# USB.net
KiCad netlist of a schematic drawn in Altium Designer
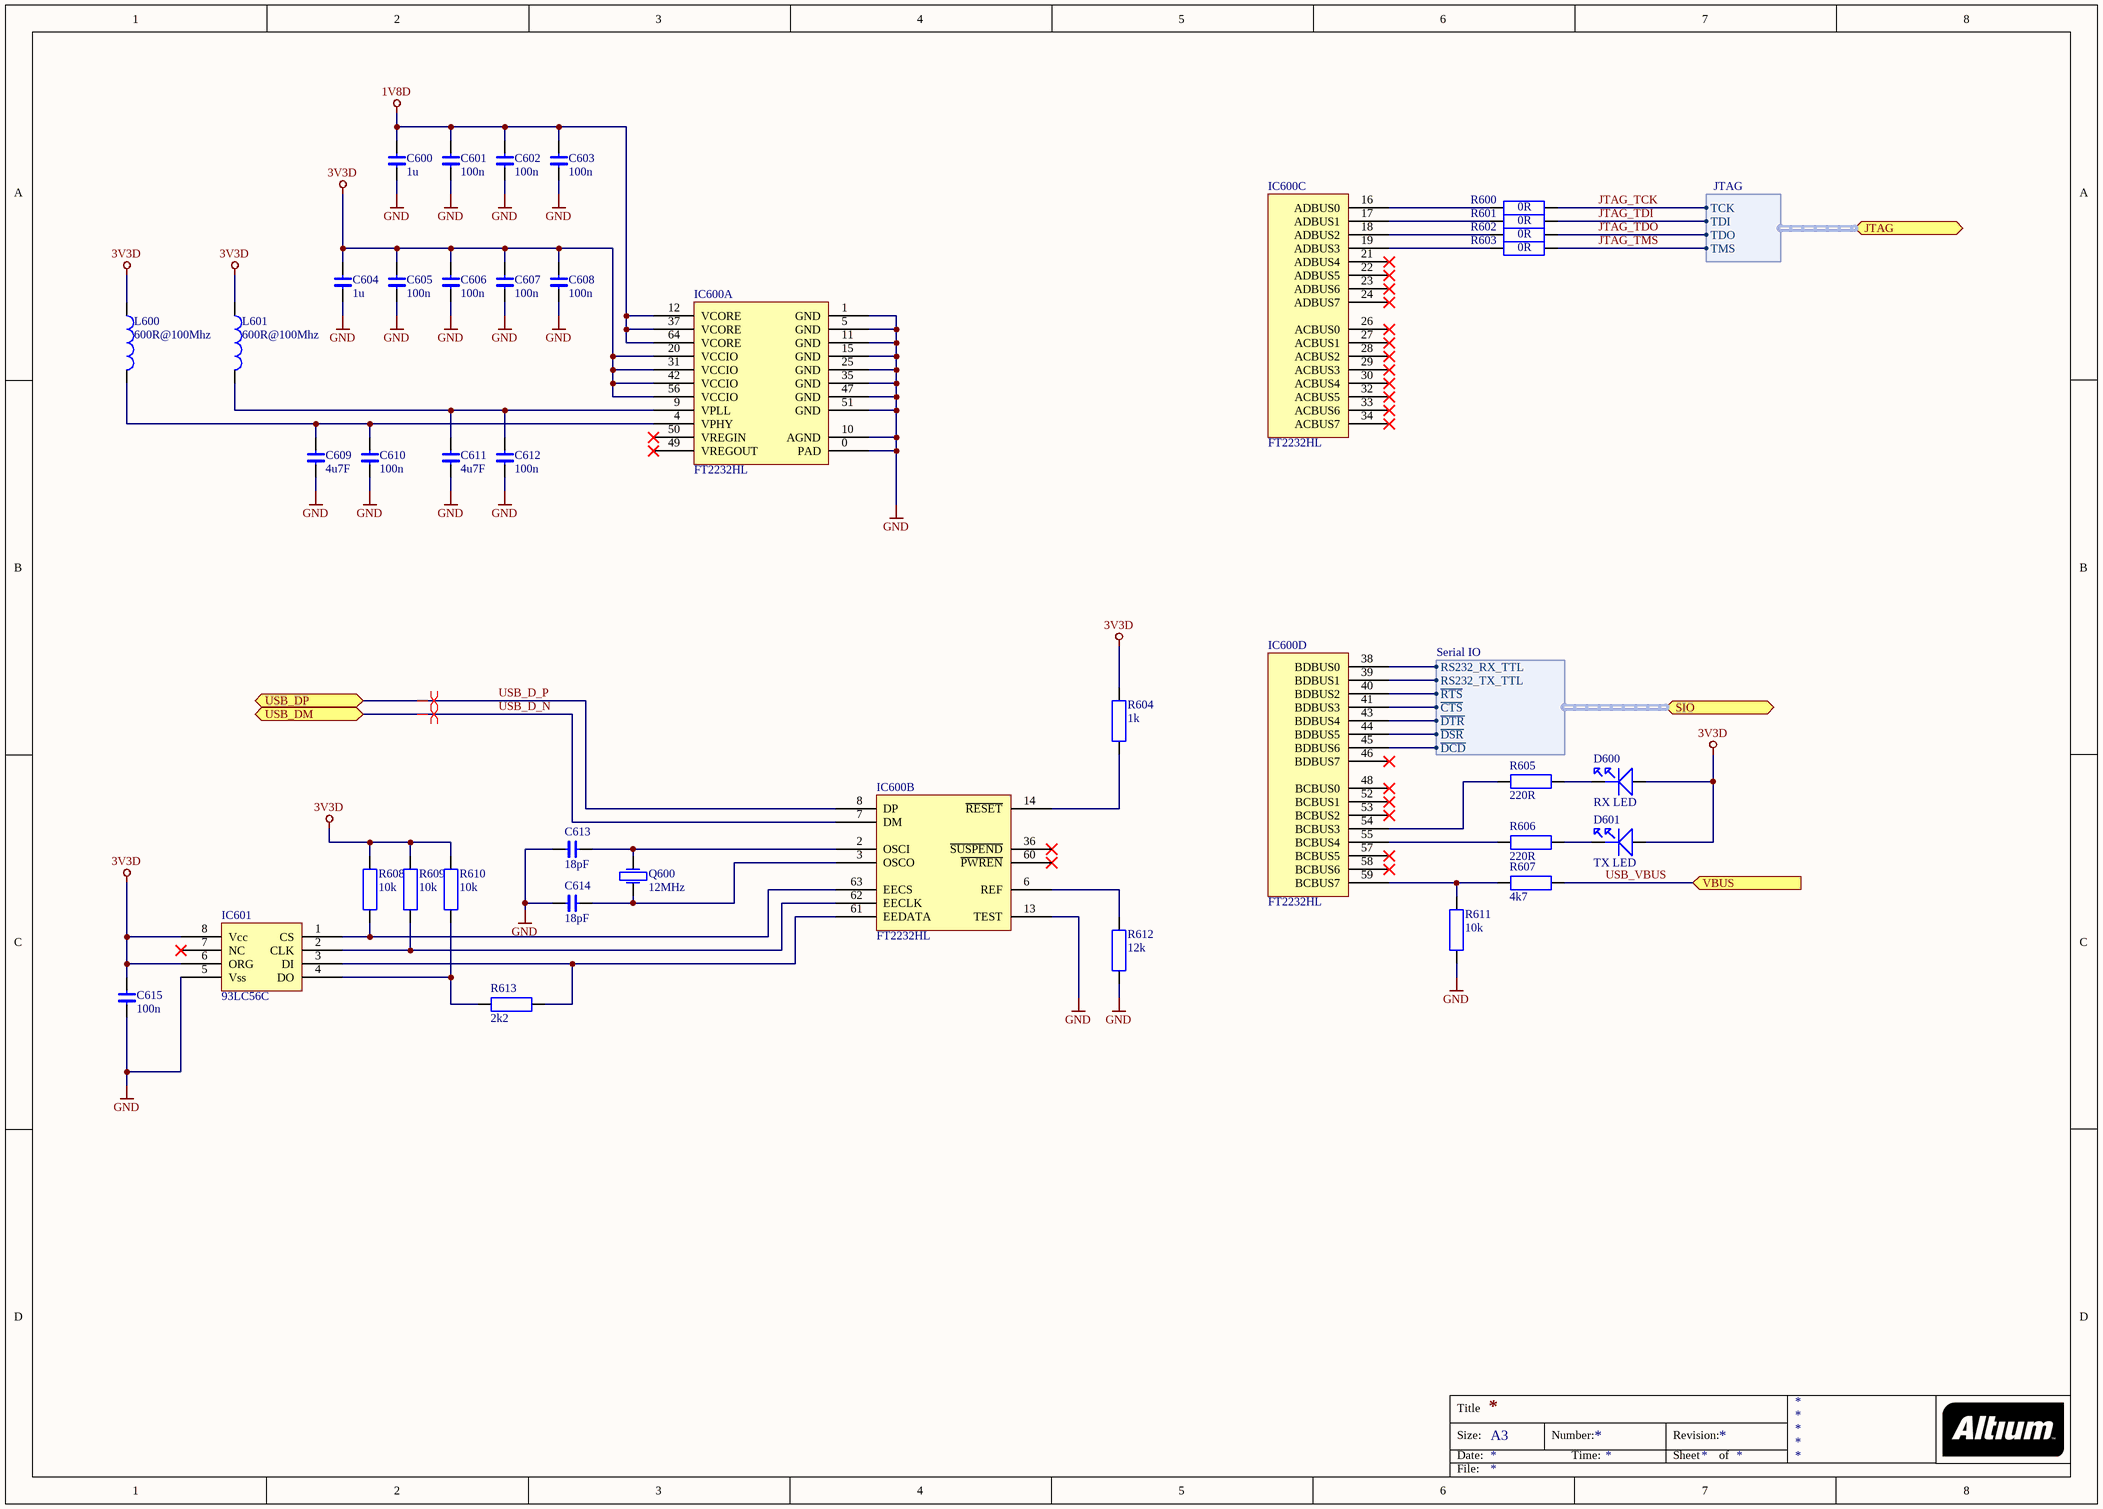
[diagram p0: USB.SchDoc]

(export (version "E")
  (design (tool "Eeschema 10.0.6"))
  (components
    (comp (ref "C600")
      (value "1u")
      (footprint "0603 SMALL OUTLINE")
      (description "C")
      (libsource (lib "RCL") (part "C"))
    )
    (comp (ref "C601")
      (value "100n")
      (footprint "0603 SMALL OUTLINE")
      (description "C")
      (libsource (lib "RCL") (part "C"))
    )
    (comp (ref "C602")
      (value "100n")
      (footprint "0603 SMALL OUTLINE")
      (description "C")
      (libsource (lib "RCL") (part "C"))
    )
    (comp (ref "C603")
      (value "100n")
      (footprint "0603 SMALL OUTLINE")
      (description "C")
      (libsource (lib "RCL") (part "C"))
    )
    (comp (ref "C604")
      (value "1u")
      (footprint "0603 SMALL OUTLINE")
      (description "C")
      (libsource (lib "RCL") (part "C"))
    )
    (comp (ref "C605")
      (value "100n")
      (footprint "0603 SMALL OUTLINE")
      (description "C")
      (libsource (lib "RCL") (part "C"))
    )
    (comp (ref "C606")
      (value "100n")
      (footprint "0603 SMALL OUTLINE")
      (description "C")
      (libsource (lib "RCL") (part "C"))
    )
    (comp (ref "C607")
      (value "100n")
      (footprint "0603 SMALL OUTLINE")
      (description "C")
      (libsource (lib "RCL") (part "C"))
    )
    (comp (ref "C608")
      (value "100n")
      (footprint "0603 SMALL OUTLINE")
      (description "C")
      (libsource (lib "RCL") (part "C"))
    )
    (comp (ref "C609")
      (value "4u7F")
      (footprint "0603 SMALL OUTLINE")
      (description "C")
      (libsource (lib "RCL") (part "C"))
    )
    (comp (ref "C610")
      (value "100n")
      (footprint "0603 SMALL OUTLINE")
      (description "C")
      (libsource (lib "RCL") (part "C"))
    )
    (comp (ref "C611")
      (value "4u7F")
      (footprint "0603 SMALL OUTLINE")
      (description "C")
      (libsource (lib "RCL") (part "C"))
    )
    (comp (ref "C612")
      (value "100n")
      (footprint "0603 SMALL OUTLINE")
      (description "C")
      (libsource (lib "RCL") (part "C"))
    )
    (comp (ref "C613")
      (value "18pF")
      (footprint "0603 SMALL OUTLINE")
      (description "C")
      (libsource (lib "RCL") (part "C"))
    )
    (comp (ref "C614")
      (value "18pF")
      (footprint "0603 SMALL OUTLINE")
      (description "C")
      (libsource (lib "RCL") (part "C"))
    )
    (comp (ref "C615")
      (value "100n")
      (footprint "0603 SMALL OUTLINE")
      (description "C")
      (libsource (lib "RCL") (part "C"))
    )
    (comp (ref "D600")
      (value "RX LED")
      (footprint "LED SMD 0603")
      (description "WURTH 150060VS75000")
      (libsource (lib "OPTO1") (part "LED SMD"))
    )
    (comp (ref "D601")
      (value "TX LED")
      (footprint "LED SMD 0603")
      (description "WURTH 150060VS75000")
      (libsource (lib "OPTO1") (part "LED SMD"))
    )
    (comp (ref "IC600")
      (value "FT2232HL")
      (footprint "64QFN")
      (description "DUAL HIGH SPEED USB TO MULTIPURPOSE UART/FIFO IC")
      (libsource (lib "Private") (part "FT2232HL"))
    )
    (comp (ref "IC601")
      (value "93LC56C")
      (footprint "MSOP8")
      (description "2K Microwire Compatible Serial EEPROM")
      (libsource (lib "Private") (part "93LC56C"))
    )
    (comp (ref "L600") (value "600R@100Mhz") (footprint "0805") (libsource (lib "RCL") (part "L")))
    (comp (ref "L601") (value "600R@100Mhz") (footprint "0805") (libsource (lib "RCL") (part "L")))
    (comp (ref "Q600")
      (value "12MHz")
      (footprint "SMD_XTAL_5x3.2")
      (description "XX MHz")
      (libsource (lib "RCL") (part "CRYSTAL"))
    )
    (comp (ref "R600")
      (value "0R")
      (footprint "0603 SMALL OUTLINE")
      (description "R")
      (libsource (lib "RCL") (part "R"))
    )
    (comp (ref "R601")
      (value "0R")
      (footprint "0603 SMALL OUTLINE")
      (description "R")
      (libsource (lib "RCL") (part "R"))
    )
    (comp (ref "R602")
      (value "0R")
      (footprint "0603 SMALL OUTLINE")
      (description "R")
      (libsource (lib "RCL") (part "R"))
    )
    (comp (ref "R603")
      (value "0R")
      (footprint "0603 SMALL OUTLINE")
      (description "R")
      (libsource (lib "RCL") (part "R"))
    )
    (comp (ref "R604")
      (value "1k")
      (footprint "0603 SMALL OUTLINE")
      (description "R")
      (libsource (lib "RCL") (part "R"))
    )
    (comp (ref "R605")
      (value "220R")
      (footprint "0603 SMALL OUTLINE")
      (description "R")
      (libsource (lib "RCL") (part "R"))
    )
    (comp (ref "R606")
      (value "220R")
      (footprint "0603 SMALL OUTLINE")
      (description "R")
      (libsource (lib "RCL") (part "R"))
    )
    (comp (ref "R607")
      (value "4k7")
      (footprint "0603 SMALL OUTLINE")
      (description "R")
      (libsource (lib "RCL") (part "R"))
    )
    (comp (ref "R608")
      (value "10k")
      (footprint "0603 SMALL OUTLINE")
      (description "R")
      (libsource (lib "RCL") (part "R"))
    )
    (comp (ref "R609")
      (value "10k")
      (footprint "0603 SMALL OUTLINE")
      (description "R")
      (libsource (lib "RCL") (part "R"))
    )
    (comp (ref "R610")
      (value "10k")
      (footprint "0603 SMALL OUTLINE")
      (description "R")
      (libsource (lib "RCL") (part "R"))
    )
    (comp (ref "R611")
      (value "10k")
      (footprint "0603 SMALL OUTLINE")
      (description "R")
      (libsource (lib "RCL") (part "R"))
    )
    (comp (ref "R612")
      (value "12k")
      (footprint "0603 SMALL OUTLINE")
      (description "R")
      (libsource (lib "RCL") (part "R"))
    )
    (comp (ref "R613")
      (value "2k2")
      (footprint "0603 SMALL OUTLINE")
      (description "R")
      (libsource (lib "RCL") (part "R"))
    )
  )
  (nets
    (net (code "4") (name "/JTAG_TCK") (class "Default")
      (node (ref "R600") (pin "2") (pinfunction "2_2") (pintype "passive"))
    )
    (net (code "5") (name "/JTAG_TDI") (class "Default")
      (node (ref "R601") (pin "2") (pinfunction "2_2") (pintype "passive"))
    )
    (net (code "6") (name "/JTAG_TDO") (class "Default")
      (node (ref "R602") (pin "2") (pinfunction "2_2") (pintype "passive"))
    )
    (net (code "7") (name "/JTAG_TMS") (class "Default")
      (node (ref "R603") (pin "2") (pinfunction "2_2") (pintype "passive"))
    )
    (net (code "8") (name "/RS232_RX_TTL") (class "Default")
      (node (ref "IC600") (pin "38") (pinfunction "BDBUS0_38") (pintype "passive"))
    )
    (net (code "9") (name "/RS232_TX_TTL") (class "Default")
      (node (ref "IC600") (pin "39") (pinfunction "BDBUS1_39") (pintype "passive"))
    )
    (net (code "10") (name "/USB_D_N") (class "Default")
      (node (ref "IC600") (pin "7") (pinfunction "DM_7") (pintype "passive"))
    )
    (net (code "11") (name "/USB_D_P") (class "Default")
      (node (ref "IC600") (pin "8") (pinfunction "DP_8") (pintype "passive"))
    )
    (net (code "12") (name "/USB_VBUS") (class "Default")
      (node (ref "R607") (pin "1") (pinfunction "1_1") (pintype "passive"))
    )
    (net (code "15") (name "/~{CTS}") (class "Default")
      (node (ref "IC600") (pin "41") (pinfunction "BDBUS3_41") (pintype "passive"))
    )
    (net (code "16") (name "/~{DCD}") (class "Default")
      (node (ref "IC600") (pin "45") (pinfunction "BDBUS6_45") (pintype "passive"))
    )
    (net (code "17") (name "/~{DSR}") (class "Default")
      (node (ref "IC600") (pin "44") (pinfunction "BDBUS5_44") (pintype "passive"))
    )
    (net (code "18") (name "/~{DTR}") (class "Default")
      (node (ref "IC600") (pin "43") (pinfunction "BDBUS4_43") (pintype "passive"))
    )
    (net (code "19") (name "/~{RTS}") (class "Default")
      (node (ref "IC600") (pin "40") (pinfunction "BDBUS2_40") (pintype "passive"))
    )
    (net (code "20") (name "1V8D") (class "Default")
      (node (ref "C600") (pin "1") (pinfunction "1_1") (pintype "passive"))
      (node (ref "C601") (pin "1") (pinfunction "1_1") (pintype "passive"))
      (node (ref "C602") (pin "1") (pinfunction "1_1") (pintype "passive"))
      (node (ref "C603") (pin "1") (pinfunction "1_1") (pintype "passive"))
      (node (ref "IC600") (pin "12") (pinfunction "VCORE_12") (pintype "passive"))
      (node (ref "IC600") (pin "37") (pinfunction "VCORE_37") (pintype "passive"))
      (node (ref "IC600") (pin "64") (pinfunction "VCORE_64") (pintype "passive"))
    )
    (net (code "21") (name "3V3D") (class "Default")
      (node (ref "C604") (pin "1") (pinfunction "1_1") (pintype "passive"))
      (node (ref "C605") (pin "1") (pinfunction "1_1") (pintype "passive"))
      (node (ref "C606") (pin "1") (pinfunction "1_1") (pintype "passive"))
      (node (ref "C607") (pin "1") (pinfunction "1_1") (pintype "passive"))
      (node (ref "C608") (pin "1") (pinfunction "1_1") (pintype "passive"))
      (node (ref "C615") (pin "1") (pinfunction "1_1") (pintype "passive"))
      (node (ref "D600") (pin "A") (pinfunction "A_A") (pintype "passive"))
      (node (ref "D601") (pin "A") (pinfunction "A_A") (pintype "passive"))
      (node (ref "IC600") (pin "20") (pinfunction "VCCIO_20") (pintype "passive"))
      (node (ref "IC600") (pin "31") (pinfunction "VCCIO_31") (pintype "passive"))
      (node (ref "IC600") (pin "42") (pinfunction "VCCIO_42") (pintype "passive"))
      (node (ref "IC600") (pin "56") (pinfunction "VCCIO_56") (pintype "passive"))
      (node (ref "IC601") (pin "6") (pinfunction "ORG_6") (pintype "passive"))
      (node (ref "IC601") (pin "8") (pinfunction "Vcc_8") (pintype "passive"))
      (node (ref "L600") (pin "1") (pinfunction "1_1") (pintype "passive"))
      (node (ref "L601") (pin "1") (pinfunction "1_1") (pintype "passive"))
      (node (ref "R604") (pin "2") (pinfunction "2_2") (pintype "passive"))
      (node (ref "R608") (pin "2") (pinfunction "2_2") (pintype "passive"))
      (node (ref "R609") (pin "2") (pinfunction "2_2") (pintype "passive"))
      (node (ref "R610") (pin "2") (pinfunction "2_2") (pintype "passive"))
    )
    (net (code "22") (name "GND") (class "Default")
      (node (ref "C600") (pin "2") (pinfunction "2_2") (pintype "passive"))
      (node (ref "C601") (pin "2") (pinfunction "2_2") (pintype "passive"))
      (node (ref "C602") (pin "2") (pinfunction "2_2") (pintype "passive"))
      (node (ref "C603") (pin "2") (pinfunction "2_2") (pintype "passive"))
      (node (ref "C604") (pin "2") (pinfunction "2_2") (pintype "passive"))
      (node (ref "C605") (pin "2") (pinfunction "2_2") (pintype "passive"))
      (node (ref "C606") (pin "2") (pinfunction "2_2") (pintype "passive"))
      (node (ref "C607") (pin "2") (pinfunction "2_2") (pintype "passive"))
      (node (ref "C608") (pin "2") (pinfunction "2_2") (pintype "passive"))
      (node (ref "C609") (pin "2") (pinfunction "2_2") (pintype "passive"))
      (node (ref "C610") (pin "2") (pinfunction "2_2") (pintype "passive"))
      (node (ref "C611") (pin "2") (pinfunction "2_2") (pintype "passive"))
      (node (ref "C612") (pin "2") (pinfunction "2_2") (pintype "passive"))
      (node (ref "C613") (pin "2") (pinfunction "2_2") (pintype "passive"))
      (node (ref "C614") (pin "2") (pinfunction "2_2") (pintype "passive"))
      (node (ref "C615") (pin "2") (pinfunction "2_2") (pintype "passive"))
      (node (ref "IC600") (pin "0") (pinfunction "PAD_0") (pintype "passive"))
      (node (ref "IC600") (pin "1") (pinfunction "GND_1") (pintype "passive"))
      (node (ref "IC600") (pin "10") (pinfunction "AGND_10") (pintype "passive"))
      (node (ref "IC600") (pin "11") (pinfunction "GND_11") (pintype "passive"))
      (node (ref "IC600") (pin "13") (pinfunction "TEST_13") (pintype "passive"))
      (node (ref "IC600") (pin "15") (pinfunction "GND_15") (pintype "passive"))
      (node (ref "IC600") (pin "25") (pinfunction "GND_25") (pintype "passive"))
      (node (ref "IC600") (pin "35") (pinfunction "GND_35") (pintype "passive"))
      (node (ref "IC600") (pin "47") (pinfunction "GND_47") (pintype "passive"))
      (node (ref "IC600") (pin "5") (pinfunction "GND_5") (pintype "passive"))
      (node (ref "IC600") (pin "51") (pinfunction "GND_51") (pintype "passive"))
      (node (ref "IC601") (pin "5") (pinfunction "Vss_5") (pintype "passive"))
      (node (ref "R611") (pin "1") (pinfunction "1_1") (pintype "passive"))
      (node (ref "R612") (pin "1") (pinfunction "1_1") (pintype "passive"))
    )
    (net (code "23") (name "Net-(D600-PadK)") (class "Default")
      (node (ref "D600") (pin "K") (pinfunction "K_K") (pintype "passive"))
      (node (ref "R605") (pin "1") (pinfunction "1_1") (pintype "passive"))
    )
    (net (code "24") (name "Net-(D601-PadK)") (class "Default")
      (node (ref "D601") (pin "K") (pinfunction "K_K") (pintype "passive"))
      (node (ref "R606") (pin "1") (pinfunction "1_1") (pintype "passive"))
    )
    (net (code "25") (name "Net-(IC600A-VPHY)") (class "Default")
      (node (ref "C609") (pin "1") (pinfunction "1_1") (pintype "passive"))
      (node (ref "C610") (pin "1") (pinfunction "1_1") (pintype "passive"))
      (node (ref "IC600") (pin "4") (pinfunction "VPHY_4") (pintype "passive"))
      (node (ref "L600") (pin "2") (pinfunction "2_2") (pintype "passive"))
    )
    (net (code "26") (name "Net-(IC600A-VPLL)") (class "Default")
      (node (ref "C611") (pin "1") (pinfunction "1_1") (pintype "passive"))
      (node (ref "C612") (pin "1") (pinfunction "1_1") (pintype "passive"))
      (node (ref "IC600") (pin "9") (pinfunction "VPLL_9") (pintype "passive"))
      (node (ref "L601") (pin "2") (pinfunction "2_2") (pintype "passive"))
    )
    (net (code "27") (name "Net-(IC600B-EECLK)") (class "Default")
      (node (ref "IC600") (pin "62") (pinfunction "EECLK_62") (pintype "passive"))
      (node (ref "IC601") (pin "2") (pinfunction "CLK_2") (pintype "passive"))
      (node (ref "R609") (pin "1") (pinfunction "1_1") (pintype "passive"))
    )
    (net (code "28") (name "Net-(IC600B-EECS)") (class "Default")
      (node (ref "IC600") (pin "63") (pinfunction "EECS_63") (pintype "passive"))
      (node (ref "IC601") (pin "1") (pinfunction "CS_1") (pintype "passive"))
      (node (ref "R608") (pin "1") (pinfunction "1_1") (pintype "passive"))
    )
    (net (code "29") (name "Net-(IC600B-EEDATA)") (class "Default")
      (node (ref "IC600") (pin "61") (pinfunction "EEDATA_61") (pintype "passive"))
      (node (ref "IC601") (pin "3") (pinfunction "DI_3") (pintype "passive"))
      (node (ref "R613") (pin "2") (pinfunction "2_2") (pintype "passive"))
    )
    (net (code "30") (name "Net-(IC600B-OSCI)") (class "Default")
      (node (ref "C613") (pin "1") (pinfunction "1_1") (pintype "passive"))
      (node (ref "IC600") (pin "2") (pinfunction "OSCI_2") (pintype "passive"))
      (node (ref "Q600") (pin "2") (pinfunction "2_2") (pintype "passive"))
    )
    (net (code "31") (name "Net-(IC600B-OSCO)") (class "Default")
      (node (ref "C614") (pin "1") (pinfunction "1_1") (pintype "passive"))
      (node (ref "IC600") (pin "3") (pinfunction "OSCO_3") (pintype "passive"))
      (node (ref "Q600") (pin "1") (pinfunction "1_1") (pintype "passive"))
    )
    (net (code "32") (name "Net-(IC600B-REF)") (class "Default")
      (node (ref "IC600") (pin "6") (pinfunction "REF_6") (pintype "passive"))
      (node (ref "R612") (pin "2") (pinfunction "2_2") (pintype "passive"))
    )
    (net (code "33") (name "Net-(IC600B-~{RESET})") (class "Default")
      (node (ref "IC600") (pin "14") (pinfunction "~{RESET}_14") (pintype "passive"))
      (node (ref "R604") (pin "1") (pinfunction "1_1") (pintype "passive"))
    )
    (net (code "34") (name "Net-(IC600C-ADBUS0)") (class "Default")
      (node (ref "IC600") (pin "16") (pinfunction "ADBUS0_16") (pintype "passive"))
      (node (ref "R600") (pin "1") (pinfunction "1_1") (pintype "passive"))
    )
    (net (code "35") (name "Net-(IC600C-ADBUS1)") (class "Default")
      (node (ref "IC600") (pin "17") (pinfunction "ADBUS1_17") (pintype "passive"))
      (node (ref "R601") (pin "1") (pinfunction "1_1") (pintype "passive"))
    )
    (net (code "36") (name "Net-(IC600C-ADBUS2)") (class "Default")
      (node (ref "IC600") (pin "18") (pinfunction "ADBUS2_18") (pintype "passive"))
      (node (ref "R602") (pin "1") (pinfunction "1_1") (pintype "passive"))
    )
    (net (code "37") (name "Net-(IC600C-ADBUS3)") (class "Default")
      (node (ref "IC600") (pin "19") (pinfunction "ADBUS3_19") (pintype "passive"))
      (node (ref "R603") (pin "1") (pinfunction "1_1") (pintype "passive"))
    )
    (net (code "38") (name "Net-(IC600D-BCBUS3)") (class "Default")
      (node (ref "IC600") (pin "54") (pinfunction "BCBUS3_54") (pintype "passive"))
      (node (ref "R605") (pin "2") (pinfunction "2_2") (pintype "passive"))
    )
    (net (code "39") (name "Net-(IC600D-BCBUS4)") (class "Default")
      (node (ref "IC600") (pin "55") (pinfunction "BCBUS4_55") (pintype "passive"))
      (node (ref "R606") (pin "2") (pinfunction "2_2") (pintype "passive"))
    )
    (net (code "40") (name "Net-(IC600D-BCBUS7)") (class "Default")
      (node (ref "IC600") (pin "59") (pinfunction "BCBUS7_59") (pintype "passive"))
      (node (ref "R607") (pin "2") (pinfunction "2_2") (pintype "passive"))
      (node (ref "R611") (pin "2") (pinfunction "2_2") (pintype "passive"))
    )
    (net (code "41") (name "Net-(IC601-DO)") (class "Default")
      (node (ref "IC601") (pin "4") (pinfunction "DO_4") (pintype "passive"))
      (node (ref "R610") (pin "1") (pinfunction "1_1") (pintype "passive"))
      (node (ref "R613") (pin "1") (pinfunction "1_1") (pintype "passive"))
    )
    (net (code "42") (name "unconnected-(IC600A-VREGIN-Pad50)") (class "Default")
      (node (ref "IC600") (pin "50") (pinfunction "VREGIN_50") (pintype "passive+no_connect"))
    )
    (net (code "43") (name "unconnected-(IC600A-VREGOUT-Pad49)") (class "Default")
      (node (ref "IC600") (pin "49") (pinfunction "VREGOUT_49") (pintype "passive+no_connect"))
    )
    (net (code "44") (name "unconnected-(IC600B-~{PWREN}-Pad60)") (class "Default")
      (node (ref "IC600") (pin "60") (pinfunction "~{PWREN}_60") (pintype "passive+no_connect"))
    )
    (net (code "45") (name "unconnected-(IC600B-~{SUSPEND}-Pad36)") (class "Default")
      (node (ref "IC600") (pin "36") (pinfunction "~{SUSPEND}_36") (pintype "passive+no_connect"))
    )
    (net (code "46") (name "unconnected-(IC600C-ACBUS0-Pad26)") (class "Default")
      (node (ref "IC600") (pin "26") (pinfunction "ACBUS0_26") (pintype "passive+no_connect"))
    )
    (net (code "47") (name "unconnected-(IC600C-ACBUS1-Pad27)") (class "Default")
      (node (ref "IC600") (pin "27") (pinfunction "ACBUS1_27") (pintype "passive+no_connect"))
    )
    (net (code "48") (name "unconnected-(IC600C-ACBUS2-Pad28)") (class "Default")
      (node (ref "IC600") (pin "28") (pinfunction "ACBUS2_28") (pintype "passive+no_connect"))
    )
    (net (code "49") (name "unconnected-(IC600C-ACBUS3-Pad29)") (class "Default")
      (node (ref "IC600") (pin "29") (pinfunction "ACBUS3_29") (pintype "passive+no_connect"))
    )
    (net (code "50") (name "unconnected-(IC600C-ACBUS4-Pad30)") (class "Default")
      (node (ref "IC600") (pin "30") (pinfunction "ACBUS4_30") (pintype "passive+no_connect"))
    )
    (net (code "51") (name "unconnected-(IC600C-ACBUS5-Pad32)") (class "Default")
      (node (ref "IC600") (pin "32") (pinfunction "ACBUS5_32") (pintype "passive+no_connect"))
    )
    (net (code "52") (name "unconnected-(IC600C-ACBUS6-Pad33)") (class "Default")
      (node (ref "IC600") (pin "33") (pinfunction "ACBUS6_33") (pintype "passive+no_connect"))
    )
    (net (code "53") (name "unconnected-(IC600C-ACBUS7-Pad34)") (class "Default")
      (node (ref "IC600") (pin "34") (pinfunction "ACBUS7_34") (pintype "passive+no_connect"))
    )
    (net (code "54") (name "unconnected-(IC600C-ADBUS4-Pad21)") (class "Default")
      (node (ref "IC600") (pin "21") (pinfunction "ADBUS4_21") (pintype "passive+no_connect"))
    )
    (net (code "55") (name "unconnected-(IC600C-ADBUS5-Pad22)") (class "Default")
      (node (ref "IC600") (pin "22") (pinfunction "ADBUS5_22") (pintype "passive+no_connect"))
    )
    (net (code "56") (name "unconnected-(IC600C-ADBUS6-Pad23)") (class "Default")
      (node (ref "IC600") (pin "23") (pinfunction "ADBUS6_23") (pintype "passive+no_connect"))
    )
    (net (code "57") (name "unconnected-(IC600C-ADBUS7-Pad24)") (class "Default")
      (node (ref "IC600") (pin "24") (pinfunction "ADBUS7_24") (pintype "passive+no_connect"))
    )
    (net (code "58") (name "unconnected-(IC600D-BCBUS0-Pad48)") (class "Default")
      (node (ref "IC600") (pin "48") (pinfunction "BCBUS0_48") (pintype "passive+no_connect"))
    )
    (net (code "59") (name "unconnected-(IC600D-BCBUS1-Pad52)") (class "Default")
      (node (ref "IC600") (pin "52") (pinfunction "BCBUS1_52") (pintype "passive+no_connect"))
    )
    (net (code "60") (name "unconnected-(IC600D-BCBUS2-Pad53)") (class "Default")
      (node (ref "IC600") (pin "53") (pinfunction "BCBUS2_53") (pintype "passive+no_connect"))
    )
    (net (code "61") (name "unconnected-(IC600D-BCBUS5-Pad57)") (class "Default")
      (node (ref "IC600") (pin "57") (pinfunction "BCBUS5_57") (pintype "passive+no_connect"))
    )
    (net (code "62") (name "unconnected-(IC600D-BCBUS6-Pad58)") (class "Default")
      (node (ref "IC600") (pin "58") (pinfunction "BCBUS6_58") (pintype "passive+no_connect"))
    )
    (net (code "63") (name "unconnected-(IC600D-BDBUS7-Pad46)") (class "Default")
      (node (ref "IC600") (pin "46") (pinfunction "BDBUS7_46") (pintype "passive+no_connect"))
    )
    (net (code "64") (name "unconnected-(IC601-NC-Pad7)") (class "Default")
      (node (ref "IC601") (pin "7") (pinfunction "NC_7") (pintype "passive+no_connect"))
    )
  )
)
